# my_foc.net
KiCad netlist of a schematic drawn in EasyEDA Pro
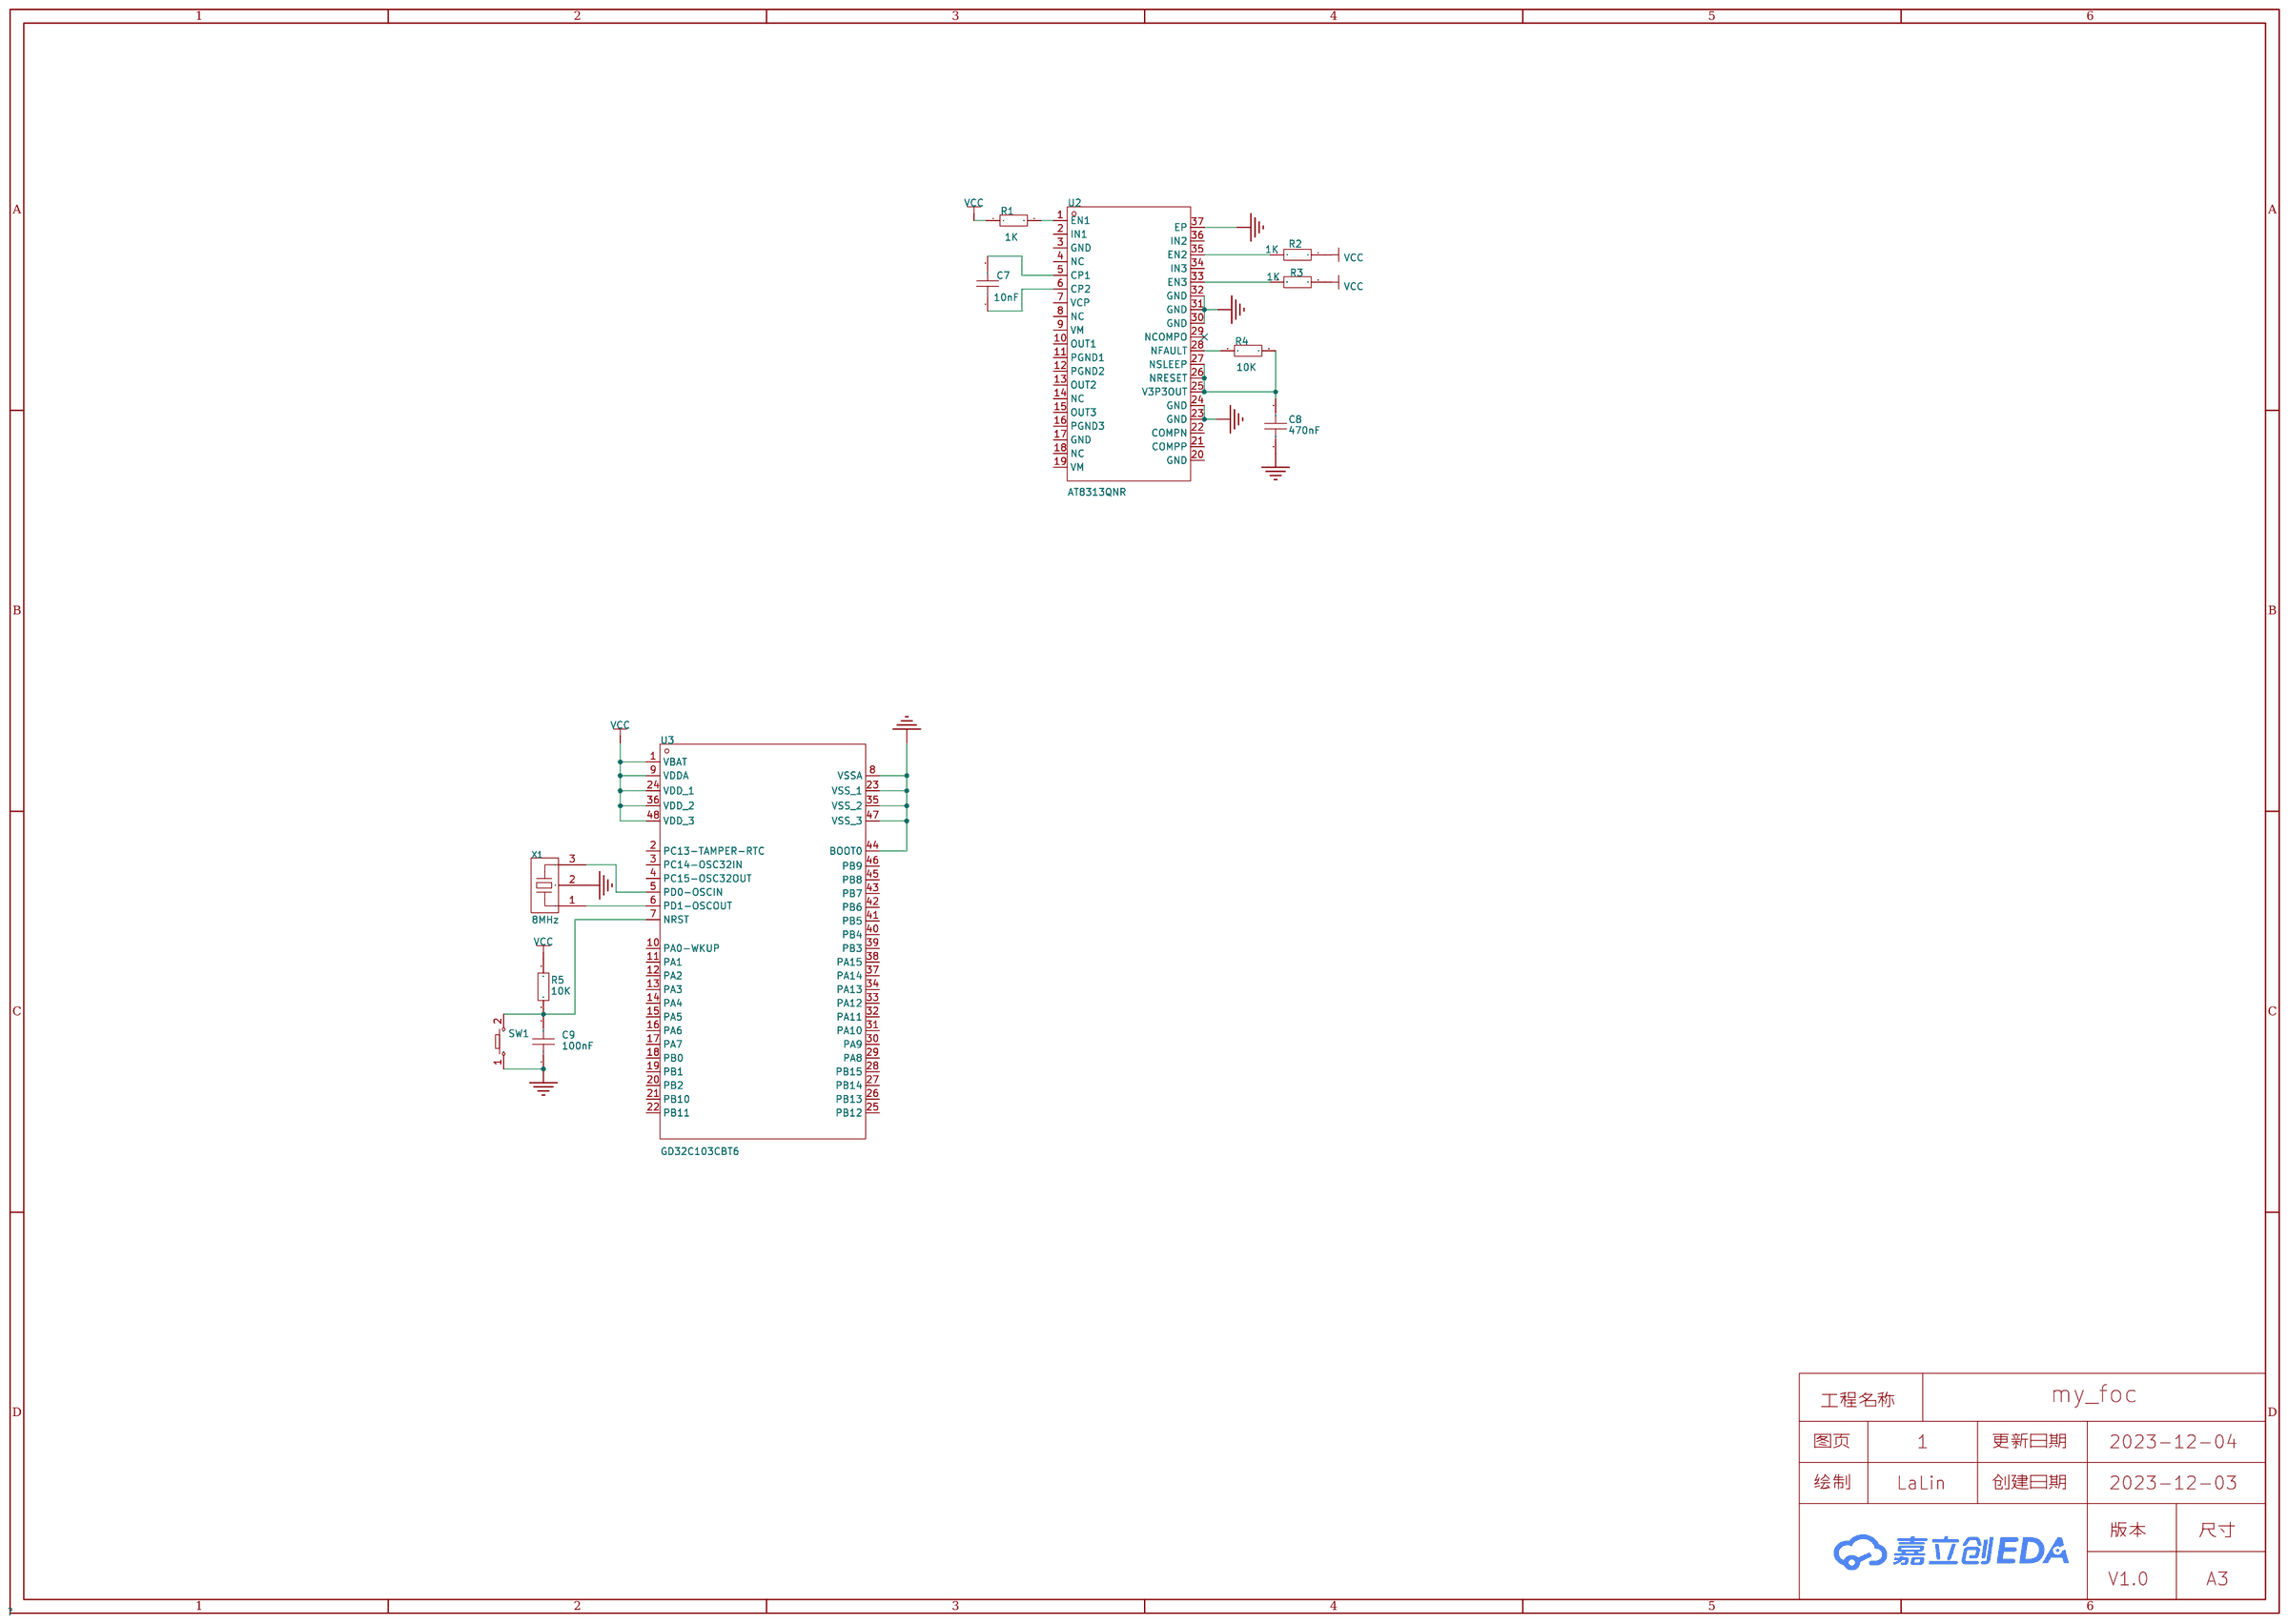
[diagram p0: schematic sheet]

(export (version "E")
  (design (tool "Eeschema 10.0.6"))
  (components
    (comp (ref "C7")
      (value "10nF")
      (footprint "easyedapro:C0603")
      (libsource (lib "easyedapro") (part "CapAcitance"))
    )
    (comp (ref "C8")
      (value "470nF")
      (footprint "easyedapro:C0603")
      (libsource (lib "easyedapro") (part "CapAcitance"))
    )
    (comp (ref "C9")
      (value "100nF")
      (footprint "easyedapro:C0603")
      (libsource (lib "easyedapro") (part "CapAcitance"))
    )
    (comp (ref "R1")
      (value "1K")
      (footprint "easyedapro:Res_1/8W")
      (libsource (lib "easyedapro") (part "电阻"))
    )
    (comp (ref "R2")
      (value "1K")
      (footprint "easyedapro:Res_1/8W")
      (libsource (lib "easyedapro") (part "电阻"))
    )
    (comp (ref "R3")
      (value "1K")
      (footprint "easyedapro:Res_1/8W")
      (libsource (lib "easyedapro") (part "电阻"))
    )
    (comp (ref "R4")
      (value "10K")
      (footprint "easyedapro:Res_1/8W")
      (libsource (lib "easyedapro") (part "电阻"))
    )
    (comp (ref "R5")
      (value "10K")
      (footprint "easyedapro:Res_1/8W")
      (libsource (lib "easyedapro") (part "电阻"))
    )
    (comp (ref "SW1")
      (value "~")
      (footprint "easyedapro:Key_SMD_3x4x2")
      (libsource (lib "easyedapro") (part "轻触按键x2"))
    )
    (comp (ref "U2")
      (value "AT8313QNR")
      (footprint "easyedapro:QFN-36_L6.0-W6.0-P0.50-TL-EP4.1")
      (fields (field (name "Manufacturer") "杭州中科微"))
      (libsource (lib "easyedapro") (part "AT8313QNR"))
    )
    (comp (ref "U3")
      (value "GD32C103CBT6")
      (footprint "easyedapro:LQFP-48_L7.0-W7.0-P0.50-LS9.0-BL")
      (description "CPU内核:ARM Cortex-M4;CPU最大主频:120MHz;程序存储容量:128KB;程序存储器类型:FLASH;GPIO端口数量:37;工作电压范围:-;RAM总容量:32KB;")
      (fields (field (name "Manufacturer") "GigaDevice(兆易创新)"))
      (libsource (lib "easyedapro") (part "GD32C103CBT6"))
    )
    (comp (ref "X1")
      (value "8MHz")
      (footprint "easyedapro:OSC-SMD_3P-L3.2-W1.3-P1.2-L")
      (description "频率:8MHz;频率容差:±0.5%;内置负载电容:10pF;谐振阻抗:40Ω;")
      (fields (field (name "Manufacturer Part") "CSTCE8M00G52-R0") (field (name "Manufacturer") "muRata(村田)"))
      (libsource (lib "easyedapro") (part "CSTCE8M00G52-R0"))
    )
  )
  (nets
    (net (code "1") (name "GND") (class "Default")
      (node (ref "C8") (pin "1") (pinfunction "1_1") (pintype "input"))
      (node (ref "C9") (pin "1") (pinfunction "1_1") (pintype "input"))
      (node (ref "SW1") (pin "1") (pinfunction "1_1") (pintype "input"))
      (node (ref "U2") (pin "23") (pinfunction "GND_23") (pintype "input"))
      (node (ref "U2") (pin "24") (pinfunction "GND_24") (pintype "input"))
      (node (ref "U2") (pin "30") (pinfunction "GND_30") (pintype "input"))
      (node (ref "U2") (pin "31") (pinfunction "GND_31") (pintype "input"))
      (node (ref "U2") (pin "32") (pinfunction "GND_32") (pintype "input"))
      (node (ref "U2") (pin "37") (pinfunction "EP_37") (pintype "input"))
      (node (ref "U3") (pin "23") (pinfunction "VSS_1_23") (pintype "unspecified"))
      (node (ref "U3") (pin "35") (pinfunction "VSS_2_35") (pintype "unspecified"))
      (node (ref "U3") (pin "44") (pinfunction "BOOT0_44") (pintype "unspecified"))
      (node (ref "U3") (pin "47") (pinfunction "VSS_3_47") (pintype "unspecified"))
      (node (ref "U3") (pin "8") (pinfunction "VSSA_8") (pintype "unspecified"))
      (node (ref "X1") (pin "2") (pinfunction "2_2") (pintype "input"))
    )
    (net (code "2") (name "Net-(U2-CP1)") (class "Default")
      (node (ref "C7") (pin "2") (pinfunction "2_2") (pintype "input"))
      (node (ref "U2") (pin "5") (pinfunction "CP1_5") (pintype "input"))
    )
    (net (code "3") (name "Net-(U2-CP2)") (class "Default")
      (node (ref "C7") (pin "1") (pinfunction "1_1") (pintype "input"))
      (node (ref "U2") (pin "6") (pinfunction "CP2_6") (pintype "input"))
    )
    (net (code "4") (name "Net-(U2-EN1)") (class "Default")
      (node (ref "R1") (pin "2") (pinfunction "2_2") (pintype "input"))
      (node (ref "U2") (pin "1") (pinfunction "EN1_1") (pintype "input"))
    )
    (net (code "5") (name "Net-(U2-EN2)") (class "Default")
      (node (ref "R2") (pin "2") (pinfunction "2_2") (pintype "input"))
      (node (ref "U2") (pin "35") (pinfunction "EN2_35") (pintype "input"))
    )
    (net (code "6") (name "Net-(U2-EN3)") (class "Default")
      (node (ref "R3") (pin "2") (pinfunction "2_2") (pintype "input"))
      (node (ref "U2") (pin "33") (pinfunction "EN3_33") (pintype "input"))
    )
    (net (code "7") (name "Net-(U2-NFAULT)") (class "Default")
      (node (ref "R4") (pin "1") (pinfunction "1_1") (pintype "input"))
      (node (ref "U2") (pin "28") (pinfunction "NFAULT_28") (pintype "input"))
    )
    (net (code "8") (name "Net-(U2-NRESET)") (class "Default")
      (node (ref "C8") (pin "2") (pinfunction "2_2") (pintype "input"))
      (node (ref "R4") (pin "2") (pinfunction "2_2") (pintype "input"))
      (node (ref "U2") (pin "25") (pinfunction "V3P3OUT_25") (pintype "input"))
      (node (ref "U2") (pin "26") (pinfunction "NRESET_26") (pintype "input"))
      (node (ref "U2") (pin "27") (pinfunction "NSLEEP_27") (pintype "input"))
    )
    (net (code "9") (name "Net-(U3-NRST)") (class "Default")
      (node (ref "C9") (pin "2") (pinfunction "2_2") (pintype "input"))
      (node (ref "R5") (pin "1") (pinfunction "1_1") (pintype "input"))
      (node (ref "SW1") (pin "2") (pinfunction "2_2") (pintype "input"))
      (node (ref "U3") (pin "7") (pinfunction "NRST_7") (pintype "unspecified"))
    )
    (net (code "10") (name "Net-(U3-PD0-OSCIN)") (class "Default")
      (node (ref "U3") (pin "5") (pinfunction "PD0-OSCIN_5") (pintype "unspecified"))
      (node (ref "X1") (pin "3") (pinfunction "3_3") (pintype "input"))
    )
    (net (code "11") (name "Net-(U3-PD1-OSCOUT)") (class "Default")
      (node (ref "U3") (pin "6") (pinfunction "PD1-OSCOUT_6") (pintype "unspecified"))
      (node (ref "X1") (pin "1") (pinfunction "1_1") (pintype "input"))
    )
    (net (code "12") (name "VCC") (class "Default")
      (node (ref "R1") (pin "1") (pinfunction "1_1") (pintype "input"))
      (node (ref "R2") (pin "1") (pinfunction "1_1") (pintype "input"))
      (node (ref "R3") (pin "1") (pinfunction "1_1") (pintype "input"))
      (node (ref "R5") (pin "2") (pinfunction "2_2") (pintype "input"))
      (node (ref "U3") (pin "1") (pinfunction "VBAT_1") (pintype "unspecified"))
      (node (ref "U3") (pin "24") (pinfunction "VDD_1_24") (pintype "unspecified"))
      (node (ref "U3") (pin "36") (pinfunction "VDD_2_36") (pintype "unspecified"))
      (node (ref "U3") (pin "48") (pinfunction "VDD_3_48") (pintype "unspecified"))
      (node (ref "U3") (pin "9") (pinfunction "VDDA_9") (pintype "unspecified"))
    )
    (net (code "13") (name "unconnected-(U2-COMPN-Pad22)") (class "Default")
      (node (ref "U2") (pin "22") (pinfunction "COMPN_22") (pintype "input"))
    )
    (net (code "14") (name "unconnected-(U2-COMPP-Pad21)") (class "Default")
      (node (ref "U2") (pin "21") (pinfunction "COMPP_21") (pintype "input"))
    )
    (net (code "15") (name "unconnected-(U2-GND-Pad3)") (class "Default")
      (node (ref "U2") (pin "3") (pinfunction "GND_3") (pintype "input"))
    )
    (net (code "16") (name "unconnected-(U2-GND-Pad17)") (class "Default")
      (node (ref "U2") (pin "17") (pinfunction "GND_17") (pintype "input"))
    )
    (net (code "17") (name "unconnected-(U2-GND-Pad20)") (class "Default")
      (node (ref "U2") (pin "20") (pinfunction "GND_20") (pintype "input"))
    )
    (net (code "18") (name "unconnected-(U2-IN1-Pad2)") (class "Default")
      (node (ref "U2") (pin "2") (pinfunction "IN1_2") (pintype "input"))
    )
    (net (code "19") (name "unconnected-(U2-IN2-Pad36)") (class "Default")
      (node (ref "U2") (pin "36") (pinfunction "IN2_36") (pintype "input"))
    )
    (net (code "20") (name "unconnected-(U2-IN3-Pad34)") (class "Default")
      (node (ref "U2") (pin "34") (pinfunction "IN3_34") (pintype "input"))
    )
    (net (code "21") (name "unconnected-(U2-NC-Pad4)") (class "Default")
      (node (ref "U2") (pin "4") (pinfunction "NC_4") (pintype "input"))
    )
    (net (code "22") (name "unconnected-(U2-NC-Pad8)") (class "Default")
      (node (ref "U2") (pin "8") (pinfunction "NC_8") (pintype "input"))
    )
    (net (code "23") (name "unconnected-(U2-NC-Pad14)") (class "Default")
      (node (ref "U2") (pin "14") (pinfunction "NC_14") (pintype "input"))
    )
    (net (code "24") (name "unconnected-(U2-NC-Pad18)") (class "Default")
      (node (ref "U2") (pin "18") (pinfunction "NC_18") (pintype "input"))
    )
    (net (code "25") (name "unconnected-(U2-NCOMPO-Pad29)") (class "Default")
      (node (ref "U2") (pin "29") (pinfunction "NCOMPO_29") (pintype "input+no_connect"))
    )
    (net (code "26") (name "unconnected-(U2-OUT1-Pad10)") (class "Default")
      (node (ref "U2") (pin "10") (pinfunction "OUT1_10") (pintype "input"))
    )
    (net (code "27") (name "unconnected-(U2-OUT2-Pad13)") (class "Default")
      (node (ref "U2") (pin "13") (pinfunction "OUT2_13") (pintype "input"))
    )
    (net (code "28") (name "unconnected-(U2-OUT3-Pad15)") (class "Default")
      (node (ref "U2") (pin "15") (pinfunction "OUT3_15") (pintype "input"))
    )
    (net (code "29") (name "unconnected-(U2-PGND1-Pad11)") (class "Default")
      (node (ref "U2") (pin "11") (pinfunction "PGND1_11") (pintype "input"))
    )
    (net (code "30") (name "unconnected-(U2-PGND2-Pad12)") (class "Default")
      (node (ref "U2") (pin "12") (pinfunction "PGND2_12") (pintype "input"))
    )
    (net (code "31") (name "unconnected-(U2-PGND3-Pad16)") (class "Default")
      (node (ref "U2") (pin "16") (pinfunction "PGND3_16") (pintype "input"))
    )
    (net (code "32") (name "unconnected-(U2-VCP-Pad7)") (class "Default")
      (node (ref "U2") (pin "7") (pinfunction "VCP_7") (pintype "input"))
    )
    (net (code "33") (name "unconnected-(U2-VM-Pad9)") (class "Default")
      (node (ref "U2") (pin "9") (pinfunction "VM_9") (pintype "input"))
    )
    (net (code "34") (name "unconnected-(U2-VM-Pad19)") (class "Default")
      (node (ref "U2") (pin "19") (pinfunction "VM_19") (pintype "input"))
    )
    (net (code "35") (name "unconnected-(U3-PA0-WKUP-Pad10)") (class "Default")
      (node (ref "U3") (pin "10") (pinfunction "PA0-WKUP_10") (pintype "unspecified"))
    )
    (net (code "36") (name "unconnected-(U3-PA1-Pad11)") (class "Default")
      (node (ref "U3") (pin "11") (pinfunction "PA1_11") (pintype "unspecified"))
    )
    (net (code "37") (name "unconnected-(U3-PA2-Pad12)") (class "Default")
      (node (ref "U3") (pin "12") (pinfunction "PA2_12") (pintype "unspecified"))
    )
    (net (code "38") (name "unconnected-(U3-PA3-Pad13)") (class "Default")
      (node (ref "U3") (pin "13") (pinfunction "PA3_13") (pintype "unspecified"))
    )
    (net (code "39") (name "unconnected-(U3-PA4-Pad14)") (class "Default")
      (node (ref "U3") (pin "14") (pinfunction "PA4_14") (pintype "unspecified"))
    )
    (net (code "40") (name "unconnected-(U3-PA5-Pad15)") (class "Default")
      (node (ref "U3") (pin "15") (pinfunction "PA5_15") (pintype "unspecified"))
    )
    (net (code "41") (name "unconnected-(U3-PA6-Pad16)") (class "Default")
      (node (ref "U3") (pin "16") (pinfunction "PA6_16") (pintype "unspecified"))
    )
    (net (code "42") (name "unconnected-(U3-PA7-Pad17)") (class "Default")
      (node (ref "U3") (pin "17") (pinfunction "PA7_17") (pintype "unspecified"))
    )
    (net (code "43") (name "unconnected-(U3-PA8-Pad29)") (class "Default")
      (node (ref "U3") (pin "29") (pinfunction "PA8_29") (pintype "unspecified"))
    )
    (net (code "44") (name "unconnected-(U3-PA9-Pad30)") (class "Default")
      (node (ref "U3") (pin "30") (pinfunction "PA9_30") (pintype "unspecified"))
    )
    (net (code "45") (name "unconnected-(U3-PA10-Pad31)") (class "Default")
      (node (ref "U3") (pin "31") (pinfunction "PA10_31") (pintype "unspecified"))
    )
    (net (code "46") (name "unconnected-(U3-PA11-Pad32)") (class "Default")
      (node (ref "U3") (pin "32") (pinfunction "PA11_32") (pintype "unspecified"))
    )
    (net (code "47") (name "unconnected-(U3-PA12-Pad33)") (class "Default")
      (node (ref "U3") (pin "33") (pinfunction "PA12_33") (pintype "unspecified"))
    )
    (net (code "48") (name "unconnected-(U3-PA13-Pad34)") (class "Default")
      (node (ref "U3") (pin "34") (pinfunction "PA13_34") (pintype "unspecified"))
    )
    (net (code "49") (name "unconnected-(U3-PA14-Pad37)") (class "Default")
      (node (ref "U3") (pin "37") (pinfunction "PA14_37") (pintype "unspecified"))
    )
    (net (code "50") (name "unconnected-(U3-PA15-Pad38)") (class "Default")
      (node (ref "U3") (pin "38") (pinfunction "PA15_38") (pintype "unspecified"))
    )
    (net (code "51") (name "unconnected-(U3-PB0-Pad18)") (class "Default")
      (node (ref "U3") (pin "18") (pinfunction "PB0_18") (pintype "unspecified"))
    )
    (net (code "52") (name "unconnected-(U3-PB1-Pad19)") (class "Default")
      (node (ref "U3") (pin "19") (pinfunction "PB1_19") (pintype "unspecified"))
    )
    (net (code "53") (name "unconnected-(U3-PB2-Pad20)") (class "Default")
      (node (ref "U3") (pin "20") (pinfunction "PB2_20") (pintype "unspecified"))
    )
    (net (code "54") (name "unconnected-(U3-PB3-Pad39)") (class "Default")
      (node (ref "U3") (pin "39") (pinfunction "PB3_39") (pintype "unspecified"))
    )
    (net (code "55") (name "unconnected-(U3-PB4-Pad40)") (class "Default")
      (node (ref "U3") (pin "40") (pinfunction "PB4_40") (pintype "unspecified"))
    )
    (net (code "56") (name "unconnected-(U3-PB5-Pad41)") (class "Default")
      (node (ref "U3") (pin "41") (pinfunction "PB5_41") (pintype "unspecified"))
    )
    (net (code "57") (name "unconnected-(U3-PB6-Pad42)") (class "Default")
      (node (ref "U3") (pin "42") (pinfunction "PB6_42") (pintype "unspecified"))
    )
    (net (code "58") (name "unconnected-(U3-PB7-Pad43)") (class "Default")
      (node (ref "U3") (pin "43") (pinfunction "PB7_43") (pintype "unspecified"))
    )
    (net (code "59") (name "unconnected-(U3-PB8-Pad45)") (class "Default")
      (node (ref "U3") (pin "45") (pinfunction "PB8_45") (pintype "unspecified"))
    )
    (net (code "60") (name "unconnected-(U3-PB9-Pad46)") (class "Default")
      (node (ref "U3") (pin "46") (pinfunction "PB9_46") (pintype "unspecified"))
    )
    (net (code "61") (name "unconnected-(U3-PB10-Pad21)") (class "Default")
      (node (ref "U3") (pin "21") (pinfunction "PB10_21") (pintype "unspecified"))
    )
    (net (code "62") (name "unconnected-(U3-PB11-Pad22)") (class "Default")
      (node (ref "U3") (pin "22") (pinfunction "PB11_22") (pintype "unspecified"))
    )
    (net (code "63") (name "unconnected-(U3-PB12-Pad25)") (class "Default")
      (node (ref "U3") (pin "25") (pinfunction "PB12_25") (pintype "unspecified"))
    )
    (net (code "64") (name "unconnected-(U3-PB13-Pad26)") (class "Default")
      (node (ref "U3") (pin "26") (pinfunction "PB13_26") (pintype "unspecified"))
    )
    (net (code "65") (name "unconnected-(U3-PB14-Pad27)") (class "Default")
      (node (ref "U3") (pin "27") (pinfunction "PB14_27") (pintype "unspecified"))
    )
    (net (code "66") (name "unconnected-(U3-PB15-Pad28)") (class "Default")
      (node (ref "U3") (pin "28") (pinfunction "PB15_28") (pintype "unspecified"))
    )
    (net (code "67") (name "unconnected-(U3-PC13-TAMPER-RTC-Pad2)") (class "Default")
      (node (ref "U3") (pin "2") (pinfunction "PC13-TAMPER-RTC_2") (pintype "unspecified"))
    )
    (net (code "68") (name "unconnected-(U3-PC14-OSC32IN-Pad3)") (class "Default")
      (node (ref "U3") (pin "3") (pinfunction "PC14-OSC32IN_3") (pintype "unspecified"))
    )
    (net (code "69") (name "unconnected-(U3-PC15-OSC32OUT-Pad4)") (class "Default")
      (node (ref "U3") (pin "4") (pinfunction "PC15-OSC32OUT_4") (pintype "unspecified"))
    )
  )
)
